# latch_circuit_RTC.net
KiCad netlist of a schematic drawn in EAGLE
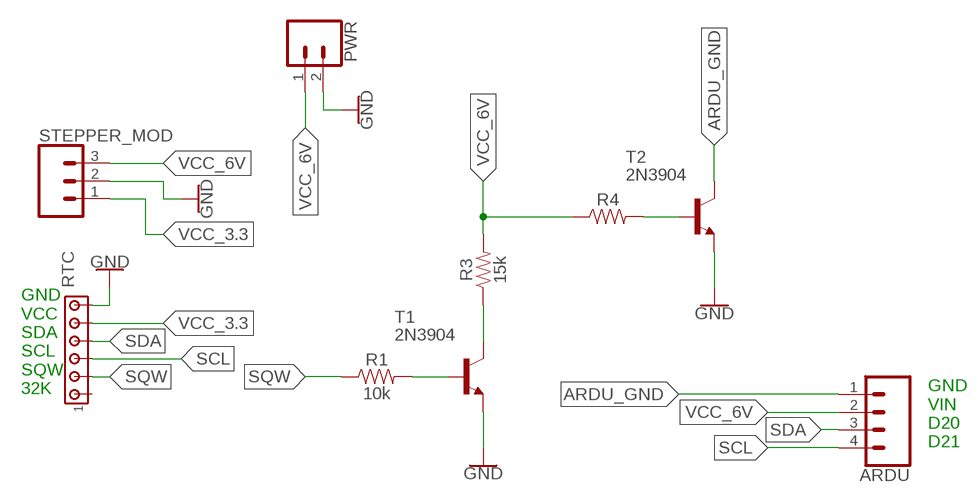
[diagram p0: schematic, sheet 1]

(export (version "E")
  (design (tool "Eeschema 10.0.6"))
  (components
    (comp (ref "ARDU")
      (value "CONN_04PTH")
      (footprint "eagle-import:1X04")
      (libsource (lib "eagle-import") (part "CONN_04PTH"))
    )
    (comp (ref "PWR")
      (value "CONN_02")
      (footprint "eagle-import:1X02")
      (libsource (lib "eagle-import") (part "CONN_02"))
    )
    (comp (ref "R1")
      (value "10k")
      (footprint "eagle-import:AXIAL-0.3")
      (libsource (lib "eagle-import") (part "10KOHM-HORIZ-1/4W-1%"))
    )
    (comp (ref "R3")
      (value "15k")
      (footprint "eagle-import:AXIAL-0.3")
      (libsource (lib "eagle-import") (part "15KOHM-HORIZ-1/4W-5%"))
    )
    (comp (ref "R4")
      (value "RESISTORAXIAL-0.3")
      (footprint "eagle-import:AXIAL-0.3")
      (libsource (lib "eagle-import") (part "RESISTORAXIAL-0.3"))
    )
    (comp (ref "RTC")
      (value "MTA06-100")
      (footprint "eagle-import:10X06MTA")
      (libsource (lib "eagle-import") (part "MTA06-100"))
    )
    (comp (ref "STEPPER_MOD")
      (value "CONN_03")
      (footprint "eagle-import:1X03")
      (libsource (lib "eagle-import") (part "CONN_03"))
    )
    (comp (ref "T1")
      (value "2N3904")
      (footprint "eagle-import:TO92")
      (libsource (lib "eagle-import") (part "2N3904"))
    )
    (comp (ref "T2")
      (value "2N3904")
      (footprint "eagle-import:TO92")
      (libsource (lib "eagle-import") (part "2N3904"))
    )
  )
  (nets
    (net (code "1") (name "ARDU_GND") (class "Default")
      (node (ref "ARDU") (pin "1") (pinfunction "1_1") (pintype "passive"))
      (node (ref "T2") (pin "1") (pinfunction "C_1") (pintype "passive"))
    )
    (net (code "2") (name "GND") (class "Default")
      (node (ref "PWR") (pin "2") (pinfunction "2_2") (pintype "passive"))
      (node (ref "RTC") (pin "6") (pinfunction "6_6") (pintype "passive"))
      (node (ref "STEPPER_MOD") (pin "2") (pinfunction "2_2") (pintype "passive"))
      (node (ref "T1") (pin "3") (pinfunction "E_3") (pintype "passive"))
      (node (ref "T2") (pin "3") (pinfunction "E_3") (pintype "passive"))
    )
    (net (code "3") (name "Net-(R1-2)") (class "Default")
      (node (ref "R1") (pin "P$2") (pinfunction "2_P$2") (pintype "passive"))
      (node (ref "T1") (pin "2") (pinfunction "B_2") (pintype "passive"))
    )
    (net (code "4") (name "Net-(R3-1)") (class "Default")
      (node (ref "R3") (pin "P$1") (pinfunction "1_P$1") (pintype "passive"))
      (node (ref "T1") (pin "1") (pinfunction "C_1") (pintype "passive"))
    )
    (net (code "5") (name "Net-(R4-2)") (class "Default")
      (node (ref "R4") (pin "P$2") (pinfunction "2_P$2") (pintype "passive"))
      (node (ref "T2") (pin "2") (pinfunction "B_2") (pintype "passive"))
    )
    (net (code "6") (name "SCL") (class "Default")
      (node (ref "ARDU") (pin "4") (pinfunction "4_4") (pintype "passive"))
      (node (ref "RTC") (pin "3") (pinfunction "3_3") (pintype "passive"))
    )
    (net (code "7") (name "SDA") (class "Default")
      (node (ref "ARDU") (pin "3") (pinfunction "3_3") (pintype "passive"))
      (node (ref "RTC") (pin "4") (pinfunction "4_4") (pintype "passive"))
    )
    (net (code "8") (name "SQW") (class "Default")
      (node (ref "R1") (pin "P$1") (pinfunction "1_P$1") (pintype "passive"))
      (node (ref "RTC") (pin "2") (pinfunction "2_2") (pintype "passive"))
    )
    (net (code "9") (name "VCC_3.3") (class "Default")
      (node (ref "RTC") (pin "5") (pinfunction "5_5") (pintype "passive"))
      (node (ref "STEPPER_MOD") (pin "1") (pinfunction "1_1") (pintype "passive"))
    )
    (net (code "10") (name "VCC_6V") (class "Default")
      (node (ref "ARDU") (pin "2") (pinfunction "2_2") (pintype "passive"))
      (node (ref "PWR") (pin "1") (pinfunction "1_1") (pintype "passive"))
      (node (ref "R3") (pin "P$2") (pinfunction "2_P$2") (pintype "passive"))
      (node (ref "R4") (pin "P$1") (pinfunction "1_P$1") (pintype "passive"))
      (node (ref "STEPPER_MOD") (pin "3") (pinfunction "3_3") (pintype "passive"))
    )
    (net (code "11") (name "unconnected-(RTC-Pad1)") (class "Default")
      (node (ref "RTC") (pin "1") (pinfunction "1_1") (pintype "passive"))
    )
  )
)
